# design.net
KiCad netlist of a schematic drawn in Altium Designer
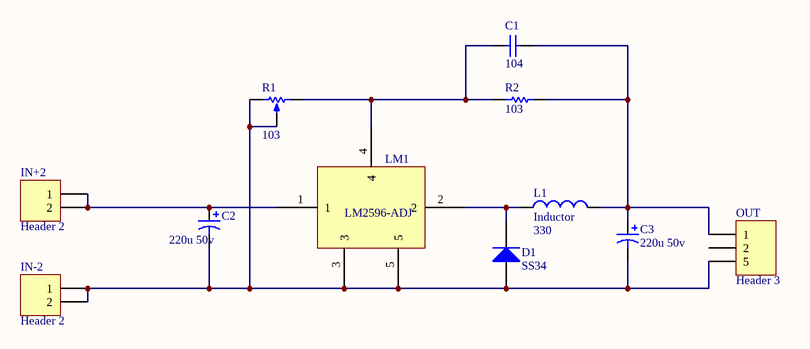
[diagram p0: 降压模块.SchDoc]

(export (version "E")
  (design (tool "Eeschema 10.0.6"))
  (components
    (comp (ref "C1")
      (value "104")
      (footprint "C1206")
      (description "Capacitor")
      (fields (field (name "PUBLISHER") "Altium Limited"))
      (libsource (lib "Miscellaneous Devices") (part "Cap"))
    )
    (comp (ref "C2")
      (value "220u 50v")
      (footprint "ABSM-1574")
      (description "Polarized Capacitor (Radial)")
      (fields (field (name "PUBLISHER") "Altium Limited"))
      (libsource (lib "Miscellaneous Devices") (part "Cap Pol1"))
    )
    (comp (ref "C3")
      (value "220u 50v")
      (footprint "ABSM-1574")
      (description "Polarized Capacitor (Radial)")
      (fields (field (name "PUBLISHER") "Altium Limited"))
      (libsource (lib "Miscellaneous Devices") (part "Cap Pol1"))
    )
    (comp (ref "D1")
      (value "SS34")
      (footprint "SMC")
      (description "Default Diode")
      (fields (field (name "PUBLISHER") "Altium Limited"))
      (libsource (lib "Miscellaneous Devices") (part "Diode"))
    )
    (comp (ref "IN+2")
      (value "Header 2")
      (footprint "HDR2X2")
      (description "Header, 2-Pin")
      (fields (field (name "PUBLISHER") "Altium Limited"))
      (libsource (lib "Miscellaneous Connectors") (part "Header 2"))
    )
    (comp (ref "IN-2")
      (value "Header 2")
      (footprint "HDR2X2")
      (description "Header, 2-Pin")
      (fields (field (name "PUBLISHER") "Altium Limited"))
      (libsource (lib "Miscellaneous Connectors") (part "Header 2"))
    )
    (comp (ref "L1")
      (value "Inductor")
      (footprint "l")
      (fields (field (name "ALTIUM_VALUE") "330") (field (name "PUBLISHER") "Altium Limited"))
      (libsource (lib "Miscellaneous Devices") (part "Inductor"))
    )
    (comp (ref "LM1") (value "Component_1") (footprint "d2") (libsource (lib "*") (part "Component_1")))
    (comp (ref "OUT")
      (value "Header 3")
      (footprint "HDR1X5")
      (description "Header, 3-Pin")
      (fields (field (name "PUBLISHER") "Altium Limited"))
      (libsource (lib "Miscellaneous Connectors") (part "Header 3"))
    )
    (comp (ref "R1")
      (value "103")
      (footprint "HDR1X5")
      (description "Potentiometer")
      (fields (field (name "PUBLISHER") "Altium Limited"))
      (libsource (lib "Miscellaneous Devices") (part "RPot"))
    )
    (comp (ref "R2")
      (value "103")
      (footprint "C1206")
      (description "Resistor")
      (fields (field (name "PUBLISHER") "Altium Limited"))
      (libsource (lib "Miscellaneous Devices") (part "Res1"))
    )
  )
  (nets
    (net (code "1") (name "Net-(C1-Pad2)") (class "Default")
      (node (ref "C1") (pin "2") (pinfunction "2_2") (pintype "passive"))
      (node (ref "C3") (pin "1") (pinfunction "1_1") (pintype "passive"))
      (node (ref "L1") (pin "0") (pinfunction "0_0") (pintype "passive"))
      (node (ref "OUT") (pin "1") (pinfunction "1_1") (pintype "passive"))
      (node (ref "R2") (pin "2") (pinfunction "2_2") (pintype "passive"))
    )
    (net (code "2") (name "Net-(C2-Pad1)") (class "Default")
      (node (ref "C2") (pin "1") (pinfunction "1_1") (pintype "passive"))
      (node (ref "IN+2") (pin "1") (pinfunction "1_1") (pintype "passive"))
      (node (ref "IN+2") (pin "2") (pinfunction "2_2") (pintype "passive"))
      (node (ref "LM1") (pin "1") (pinfunction "1_1") (pintype "passive"))
    )
    (net (code "3") (name "Net-(D1-A)") (class "Default")
      (node (ref "C2") (pin "2") (pinfunction "2_2") (pintype "passive"))
      (node (ref "C3") (pin "2") (pinfunction "2_2") (pintype "passive"))
      (node (ref "D1") (pin "1") (pinfunction "A_1") (pintype "passive"))
      (node (ref "IN-2") (pin "1") (pinfunction "1_1") (pintype "passive"))
      (node (ref "IN-2") (pin "2") (pinfunction "2_2") (pintype "passive"))
      (node (ref "LM1") (pin "3") (pinfunction "3_3") (pintype "passive"))
      (node (ref "LM1") (pin "5") (pinfunction "5_5") (pintype "passive"))
      (node (ref "OUT") (pin "5") (pinfunction "5_5") (pintype "passive"))
      (node (ref "R1") (pin "3") (pinfunction "TAP_3") (pintype "passive"))
      (node (ref "R1") (pin "5") (pinfunction "TOP_5") (pintype "passive"))
    )
    (net (code "4") (name "Net-(D1-K)") (class "Default")
      (node (ref "D1") (pin "2") (pinfunction "K_2") (pintype "passive"))
      (node (ref "L1") (pin "1") (pinfunction "1_1") (pintype "passive"))
      (node (ref "LM1") (pin "2") (pinfunction "2_2") (pintype "passive"))
    )
    (net (code "5") (name "Net-(R1-BOT)") (class "Default")
      (node (ref "C1") (pin "1") (pinfunction "1_1") (pintype "passive"))
      (node (ref "LM1") (pin "4") (pinfunction "4_4") (pintype "passive"))
      (node (ref "R1") (pin "1") (pinfunction "BOT_1") (pintype "passive"))
      (node (ref "R2") (pin "1") (pinfunction "1_1") (pintype "passive"))
    )
    (net (code "6") (name "unconnected-(OUT-Pad2)") (class "Default")
      (node (ref "OUT") (pin "2") (pinfunction "2_2") (pintype "passive"))
    )
  )
)
